# subRelayOut.net
KiCad netlist of a schematic drawn in Altium Designer
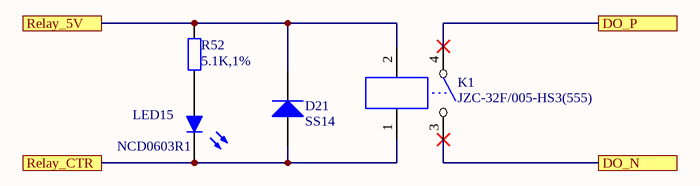
[diagram p0: subRelayOut.SchDoc]

(export (version "E")
  (design (tool "Eeschema 10.0.6"))
  (components
    (comp (ref "D21")
      (value "SS14")
      (footprint "SMA_L4.4-W2.8-LS5.4-RD")
      (description "Default Diode")
      (fields (field (name "PUBLISHER") "Altium Limited"))
      (libsource (lib "Miscellaneous Devices") (part "Diode"))
    )
    (comp (ref "K1")
      (value "JZC-32F/005-HS3(555)")
      (footprint "RELAY-TH_JZC-32F-XXXHXX")
      (libsource (lib "Schlib1") (part "JZC-32F/005-HS3(555)"))
    )
    (comp (ref "LED15")
      (value "NCD0603R1")
      (footprint "LED0603-RD")
      (description "Typical INFRARED GaAs LED")
      (libsource (lib "Schlib1") (part "LED0603"))
    )
    (comp (ref "R52")
      (value "5.1K,1%")
      (footprint "R0603")
      (description "电阻")
      (libsource (lib "电阻电容") (part "电阻"))
    )
  )
  (nets
    (net (code "1") (name "/DO_N") (class "Default")
      (node (ref "K1") (pin "3") (pinfunction "3_3") (pintype "passive+no_connect"))
    )
    (net (code "2") (name "/DO_P") (class "Default")
      (node (ref "K1") (pin "4") (pinfunction "4_4") (pintype "passive+no_connect"))
    )
    (net (code "3") (name "/Relay_5V") (class "Default")
      (node (ref "D21") (pin "2") (pinfunction "K_2") (pintype "passive"))
      (node (ref "K1") (pin "2") (pinfunction "2_2") (pintype "passive"))
      (node (ref "R52") (pin "1") (pinfunction "1_1") (pintype "passive"))
    )
    (net (code "4") (name "/Relay_CTR") (class "Default")
      (node (ref "D21") (pin "1") (pinfunction "A_1") (pintype "passive"))
      (node (ref "K1") (pin "1") (pinfunction "1_1") (pintype "passive"))
      (node (ref "LED15") (pin "1") (pinfunction "K_1") (pintype "passive"))
    )
    (net (code "5") (name "Net-(LED15-A)") (class "Default")
      (node (ref "LED15") (pin "2") (pinfunction "A_2") (pintype "passive"))
      (node (ref "R52") (pin "2") (pinfunction "2_2") (pintype "passive"))
    )
  )
)
